# drive_pcb.net
KiCad netlist of a schematic drawn in EAGLE
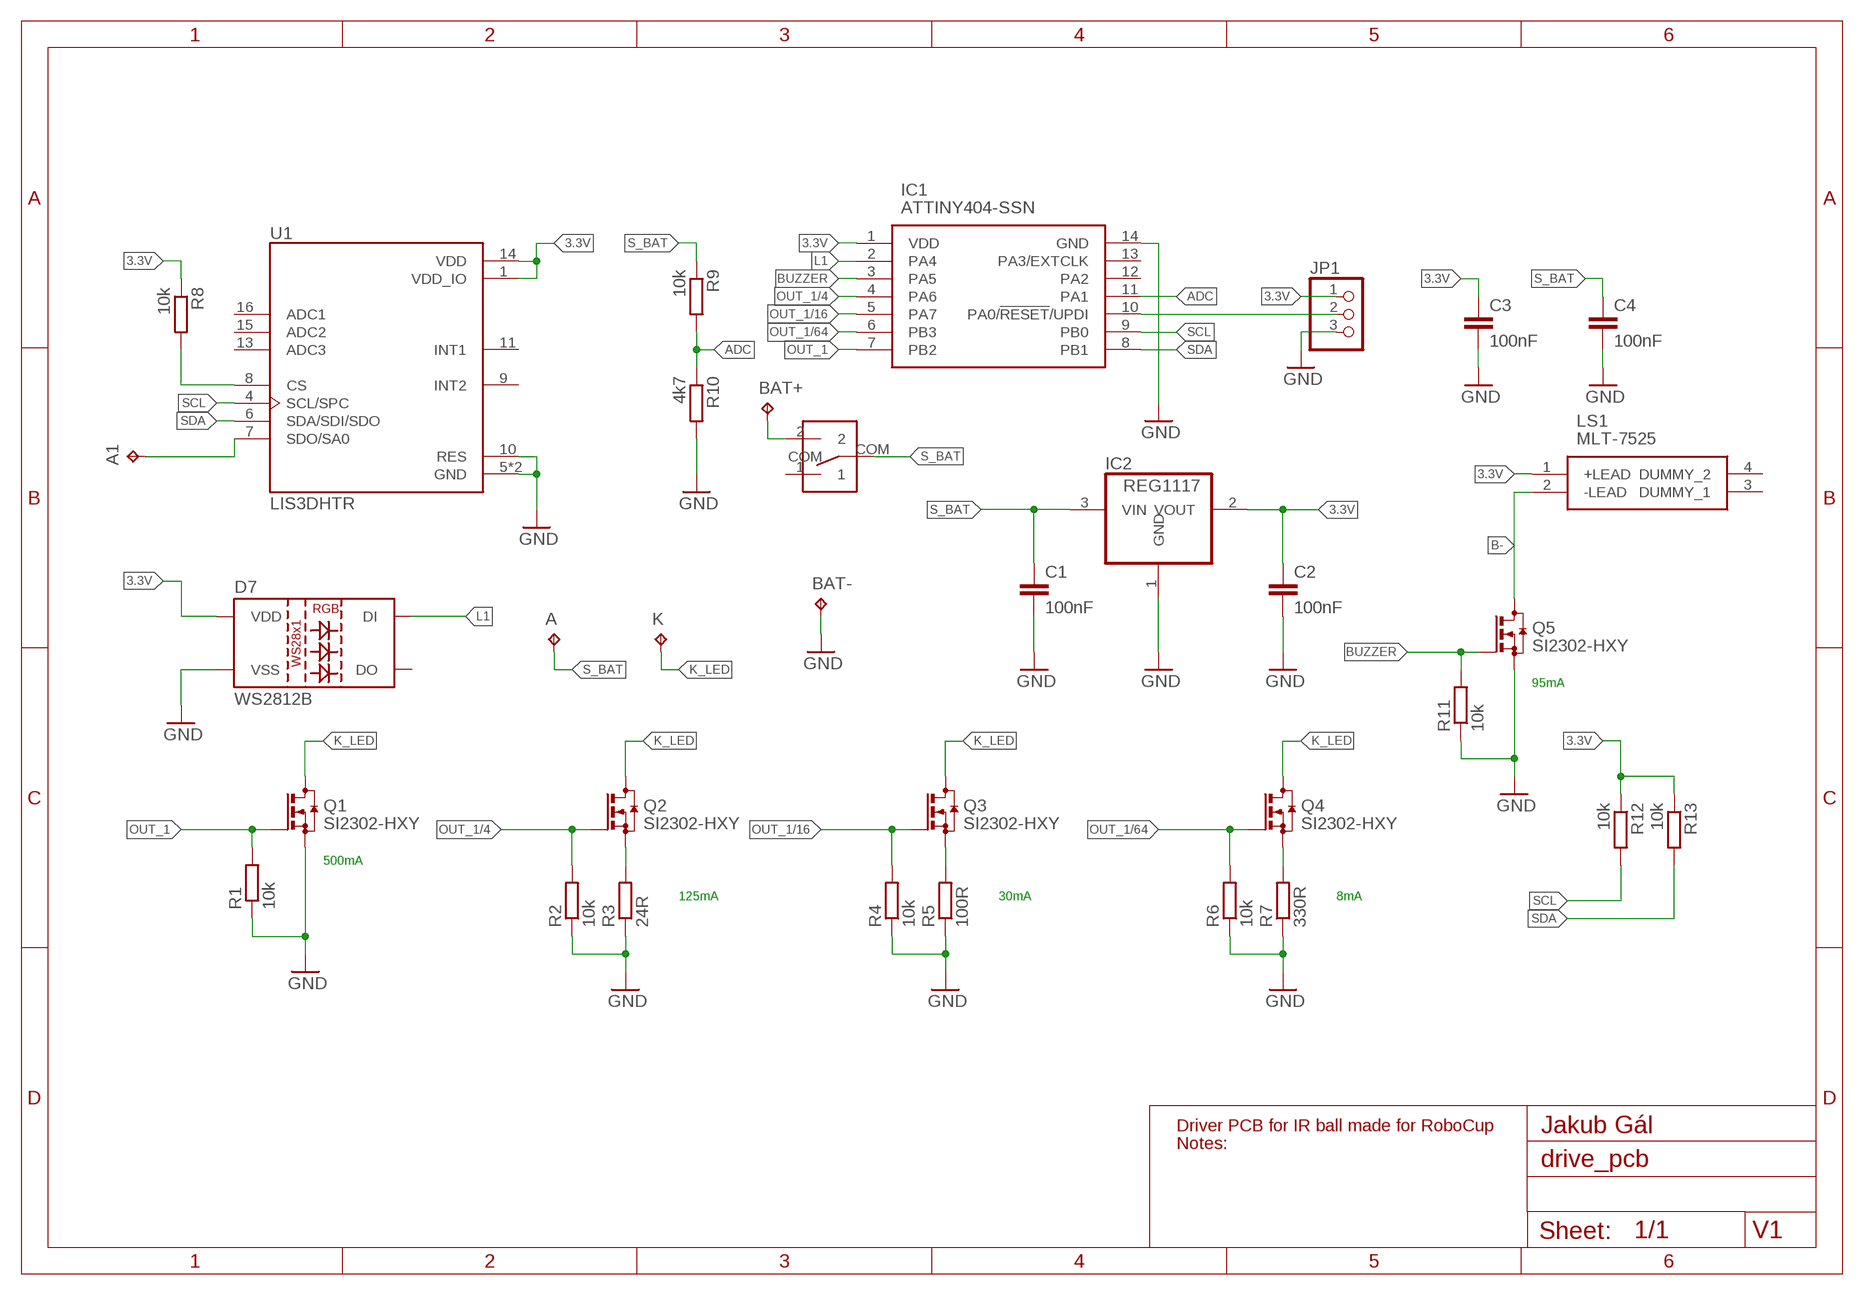
[diagram p0: schematic, sheet 1]

(export (version "E")
  (design (tool "Eeschema 10.0.6"))
  (components
    (comp (ref "A")
      (value "TPB1,27")
      (footprint "eagle-import:B1,27")
      (libsource (lib "eagle-import") (part "TPB1,27"))
    )
    (comp (ref "A1")
      (value "TPB1,27")
      (footprint "eagle-import:B1,27")
      (libsource (lib "eagle-import") (part "TPB1,27"))
    )
    (comp (ref "BAT+")
      (value "TPB1,27")
      (footprint "eagle-import:B1,27")
      (libsource (lib "eagle-import") (part "TPB1,27"))
    )
    (comp (ref "BAT-")
      (value "TPB1,27")
      (footprint "eagle-import:B1,27")
      (libsource (lib "eagle-import") (part "TPB1,27"))
    )
    (comp (ref "C1")
      (value "100nF")
      (footprint "eagle-import:C0603")
      (libsource (lib "eagle-import") (part "C-EUC0603"))
    )
    (comp (ref "C2")
      (value "100nF")
      (footprint "eagle-import:C0603")
      (libsource (lib "eagle-import") (part "C-EUC0603"))
    )
    (comp (ref "C3")
      (value "100nF")
      (footprint "eagle-import:C0603")
      (libsource (lib "eagle-import") (part "C-EUC0603"))
    )
    (comp (ref "C4")
      (value "100nF")
      (footprint "eagle-import:C0603")
      (libsource (lib "eagle-import") (part "C-EUC0603"))
    )
    (comp (ref "D7")
      (value "WS2812B")
      (footprint "eagle-import:WS2812B")
      (libsource (lib "eagle-import") (part "WS2812B"))
    )
    (comp (ref "IC1")
      (value "ATTINY404-SSN")
      (footprint "eagle-import:SOIC127P600X175-14N")
      (fields (field (name "MOUSER_PART_NUMBER") "579-ATTINY404-SSN"))
      (libsource (lib "eagle-import") (part "ATTINY404-SSN"))
    )
    (comp (ref "IC2")
      (value "REG1117")
      (footprint "eagle-import:SOT223")
      (libsource (lib "eagle-import") (part "REG1117"))
    )
    (comp (ref "JP1")
      (value "PINHD-1X3")
      (footprint "eagle-import:1X03")
      (libsource (lib "eagle-import") (part "PINHD-1X3"))
    )
    (comp (ref "K")
      (value "TPB1,27")
      (footprint "eagle-import:B1,27")
      (libsource (lib "eagle-import") (part "TPB1,27"))
    )
    (comp (ref "LS1")
      (value "MLT-7525")
      (footprint "eagle-import:MLT7525")
      (libsource (lib "eagle-import") (part "MLT-7525"))
    )
    (comp (ref "Q1")
      (value "SI2302-HXY")
      (footprint "eagle-import:SOT23")
      (libsource (lib "eagle-import") (part "BSS123"))
    )
    (comp (ref "Q2")
      (value "SI2302-HXY")
      (footprint "eagle-import:SOT23")
      (libsource (lib "eagle-import") (part "BSS123"))
    )
    (comp (ref "Q3")
      (value "SI2302-HXY")
      (footprint "eagle-import:SOT23")
      (libsource (lib "eagle-import") (part "BSS123"))
    )
    (comp (ref "Q4")
      (value "SI2302-HXY")
      (footprint "eagle-import:SOT23")
      (libsource (lib "eagle-import") (part "BSS123"))
    )
    (comp (ref "Q5")
      (value "SI2302-HXY")
      (footprint "eagle-import:SOT23")
      (libsource (lib "eagle-import") (part "BSS123"))
    )
    (comp (ref "R1")
      (value "10k")
      (footprint "eagle-import:R0603")
      (libsource (lib "eagle-import") (part "R-EU_R0603"))
    )
    (comp (ref "R2")
      (value "10k")
      (footprint "eagle-import:R0603")
      (libsource (lib "eagle-import") (part "R-EU_R0603"))
    )
    (comp (ref "R3")
      (value "24R")
      (footprint "eagle-import:R0603")
      (libsource (lib "eagle-import") (part "R-EU_R0603"))
    )
    (comp (ref "R4")
      (value "10k")
      (footprint "eagle-import:R0603")
      (libsource (lib "eagle-import") (part "R-EU_R0603"))
    )
    (comp (ref "R5")
      (value "100R")
      (footprint "eagle-import:R0603")
      (libsource (lib "eagle-import") (part "R-EU_R0603"))
    )
    (comp (ref "R6")
      (value "10k")
      (footprint "eagle-import:R0603")
      (libsource (lib "eagle-import") (part "R-EU_R0603"))
    )
    (comp (ref "R7")
      (value "330R")
      (footprint "eagle-import:R0603")
      (libsource (lib "eagle-import") (part "R-EU_R0603"))
    )
    (comp (ref "R8")
      (value "10k")
      (footprint "eagle-import:R0603")
      (libsource (lib "eagle-import") (part "R-EU_R0603"))
    )
    (comp (ref "R9")
      (value "10k")
      (footprint "eagle-import:R0603")
      (libsource (lib "eagle-import") (part "R-EU_R0603"))
    )
    (comp (ref "R10")
      (value "4k7")
      (footprint "eagle-import:R0603")
      (libsource (lib "eagle-import") (part "R-EU_R0603"))
    )
    (comp (ref "R11")
      (value "10k")
      (footprint "eagle-import:R0603")
      (libsource (lib "eagle-import") (part "R-EU_R0603"))
    )
    (comp (ref "R12")
      (value "10k")
      (footprint "eagle-import:R0603")
      (libsource (lib "eagle-import") (part "R-EU_R0603"))
    )
    (comp (ref "R13")
      (value "10k")
      (footprint "eagle-import:R0603")
      (libsource (lib "eagle-import") (part "R-EU_R0603"))
    )
    (comp (ref "U$1")
      (value "SK12D07VG4")
      (footprint "eagle-import:SK12D07VG4")
      (fields (field (name "MF") "C&K"))
      (libsource (lib "eagle-import") (part "SK12D07VG4"))
    )
    (comp (ref "U1")
      (value "LIS3DHTR")
      (footprint "eagle-import:XDCR_LIS3DHTR")
      (fields (field (name "MF") "STMicroelectronics"))
      (libsource (lib "eagle-import") (part "LIS3DHTR"))
    )
  )
  (nets
    (net (code "1") (name "3.3V") (class "Default")
      (node (ref "C2") (pin "1") (pinfunction "1_1") (pintype "passive"))
      (node (ref "C3") (pin "1") (pinfunction "1_1") (pintype "passive"))
      (node (ref "D7") (pin "1") (pinfunction "VDD_1") (pintype "bidirectional"))
      (node (ref "IC1") (pin "1") (pinfunction "VDD_1") (pintype "bidirectional"))
      (node (ref "IC2") (pin "2") (pinfunction "VOUT_2") (pintype "output"))
      (node (ref "JP1") (pin "1") (pinfunction "1_1") (pintype "passive"))
      (node (ref "LS1") (pin "1") (pinfunction "+LEAD_1") (pintype "bidirectional"))
      (node (ref "R12") (pin "1") (pinfunction "1_1") (pintype "passive"))
      (node (ref "R13") (pin "1") (pinfunction "1_1") (pintype "passive"))
      (node (ref "R8") (pin "1") (pinfunction "1_1") (pintype "passive"))
      (node (ref "U1") (pin "1") (pinfunction "VDD_IO_1") (pintype "power_in"))
      (node (ref "U1") (pin "14") (pinfunction "VDD_14") (pintype "power_in"))
    )
    (net (code "2") (name "ADC") (class "Default")
      (node (ref "IC1") (pin "11") (pinfunction "PA1_11") (pintype "bidirectional"))
      (node (ref "R10") (pin "1") (pinfunction "1_1") (pintype "passive"))
      (node (ref "R9") (pin "2") (pinfunction "2_2") (pintype "passive"))
    )
    (net (code "3") (name "B-") (class "Default")
      (node (ref "LS1") (pin "2") (pinfunction "-LEAD_2") (pintype "bidirectional"))
      (node (ref "Q5") (pin "3") (pinfunction "D_3") (pintype "passive"))
    )
    (net (code "4") (name "BUZZER") (class "Default")
      (node (ref "IC1") (pin "3") (pinfunction "PA5_3") (pintype "bidirectional"))
      (node (ref "Q5") (pin "1") (pinfunction "G_1") (pintype "passive"))
      (node (ref "R11") (pin "2") (pinfunction "2_2") (pintype "passive"))
    )
    (net (code "5") (name "GND") (class "Default")
      (node (ref "BAT-") (pin "TP") (pinfunction "TP_TP") (pintype "input"))
      (node (ref "C1") (pin "2") (pinfunction "2_2") (pintype "passive"))
      (node (ref "C2") (pin "2") (pinfunction "2_2") (pintype "passive"))
      (node (ref "C3") (pin "2") (pinfunction "2_2") (pintype "passive"))
      (node (ref "C4") (pin "2") (pinfunction "2_2") (pintype "passive"))
      (node (ref "D7") (pin "3") (pinfunction "VSS_3") (pintype "bidirectional"))
      (node (ref "IC1") (pin "14") (pinfunction "GND_14") (pintype "bidirectional"))
      (node (ref "IC2") (pin "1") (pinfunction "GND_1") (pintype "power_in"))
      (node (ref "JP1") (pin "3") (pinfunction "3_3") (pintype "passive"))
      (node (ref "Q1") (pin "2") (pinfunction "S_2") (pintype "passive"))
      (node (ref "Q5") (pin "2") (pinfunction "S_2") (pintype "passive"))
      (node (ref "R1") (pin "1") (pinfunction "1_1") (pintype "passive"))
      (node (ref "R10") (pin "2") (pinfunction "2_2") (pintype "passive"))
      (node (ref "R11") (pin "1") (pinfunction "1_1") (pintype "passive"))
      (node (ref "R2") (pin "1") (pinfunction "1_1") (pintype "passive"))
      (node (ref "R3") (pin "1") (pinfunction "1_1") (pintype "passive"))
      (node (ref "R4") (pin "1") (pinfunction "1_1") (pintype "passive"))
      (node (ref "R5") (pin "1") (pinfunction "1_1") (pintype "passive"))
      (node (ref "R6") (pin "1") (pinfunction "1_1") (pintype "passive"))
      (node (ref "R7") (pin "1") (pinfunction "1_1") (pintype "passive"))
      (node (ref "U1") (pin "10") (pinfunction "RES_10") (pintype "passive"))
      (node (ref "U1") (pin "12") (pinfunction "GND_12") (pintype "power_in"))
      (node (ref "U1") (pin "5") (pinfunction "GND_5") (pintype "power_in"))
    )
    (net (code "6") (name "K_LED") (class "Default")
      (node (ref "K") (pin "TP") (pinfunction "TP_TP") (pintype "input"))
      (node (ref "Q1") (pin "3") (pinfunction "D_3") (pintype "passive"))
      (node (ref "Q2") (pin "3") (pinfunction "D_3") (pintype "passive"))
      (node (ref "Q3") (pin "3") (pinfunction "D_3") (pintype "passive"))
      (node (ref "Q4") (pin "3") (pinfunction "D_3") (pintype "passive"))
    )
    (net (code "7") (name "L1") (class "Default")
      (node (ref "D7") (pin "4") (pinfunction "DI_4") (pintype "bidirectional"))
      (node (ref "IC1") (pin "2") (pinfunction "PA4_2") (pintype "bidirectional"))
    )
    (net (code "8") (name "Net-(BAT+-PadTP)") (class "Default")
      (node (ref "BAT+") (pin "TP") (pinfunction "TP_TP") (pintype "input"))
      (node (ref "U$1") (pin "2") (pinfunction "2_2") (pintype "bidirectional"))
    )
    (net (code "9") (name "Net-(IC1-PA0{slash}~{RESET}{slash}UPDI)") (class "Default")
      (node (ref "IC1") (pin "10") (pinfunction "PA0/~{RESET}/UPDI_10") (pintype "bidirectional"))
      (node (ref "JP1") (pin "2") (pinfunction "2_2") (pintype "passive"))
    )
    (net (code "10") (name "Net-(Q2-S)") (class "Default")
      (node (ref "Q2") (pin "2") (pinfunction "S_2") (pintype "passive"))
      (node (ref "R3") (pin "2") (pinfunction "2_2") (pintype "passive"))
    )
    (net (code "11") (name "Net-(Q3-S)") (class "Default")
      (node (ref "Q3") (pin "2") (pinfunction "S_2") (pintype "passive"))
      (node (ref "R5") (pin "2") (pinfunction "2_2") (pintype "passive"))
    )
    (net (code "12") (name "Net-(Q4-S)") (class "Default")
      (node (ref "Q4") (pin "2") (pinfunction "S_2") (pintype "passive"))
      (node (ref "R7") (pin "2") (pinfunction "2_2") (pintype "passive"))
    )
    (net (code "13") (name "Net-(U1-CS)") (class "Default")
      (node (ref "R8") (pin "2") (pinfunction "2_2") (pintype "passive"))
      (node (ref "U1") (pin "8") (pinfunction "CS_8") (pintype "input"))
    )
    (net (code "14") (name "Net-(U1-SDO{slash}SA0)") (class "Default")
      (node (ref "A1") (pin "TP") (pinfunction "TP_TP") (pintype "input"))
      (node (ref "U1") (pin "7") (pinfunction "SDO/SA0_7") (pintype "bidirectional"))
    )
    (net (code "15") (name "OUT_1") (class "Default")
      (node (ref "IC1") (pin "7") (pinfunction "PB2_7") (pintype "bidirectional"))
      (node (ref "Q1") (pin "1") (pinfunction "G_1") (pintype "passive"))
      (node (ref "R1") (pin "2") (pinfunction "2_2") (pintype "passive"))
    )
    (net (code "16") (name "OUT_1{slash}4") (class "Default")
      (node (ref "IC1") (pin "4") (pinfunction "PA6_4") (pintype "bidirectional"))
      (node (ref "Q2") (pin "1") (pinfunction "G_1") (pintype "passive"))
      (node (ref "R2") (pin "2") (pinfunction "2_2") (pintype "passive"))
    )
    (net (code "17") (name "OUT_1{slash}16") (class "Default")
      (node (ref "IC1") (pin "5") (pinfunction "PA7_5") (pintype "bidirectional"))
      (node (ref "Q3") (pin "1") (pinfunction "G_1") (pintype "passive"))
      (node (ref "R4") (pin "2") (pinfunction "2_2") (pintype "passive"))
    )
    (net (code "18") (name "OUT_1{slash}64") (class "Default")
      (node (ref "IC1") (pin "6") (pinfunction "PB3_6") (pintype "bidirectional"))
      (node (ref "Q4") (pin "1") (pinfunction "G_1") (pintype "passive"))
      (node (ref "R6") (pin "2") (pinfunction "2_2") (pintype "passive"))
    )
    (net (code "19") (name "SCL") (class "Default")
      (node (ref "IC1") (pin "9") (pinfunction "PB0_9") (pintype "bidirectional"))
      (node (ref "R12") (pin "2") (pinfunction "2_2") (pintype "passive"))
      (node (ref "U1") (pin "4") (pinfunction "SCL/SPC_4") (pintype "input"))
    )
    (net (code "20") (name "SDA") (class "Default")
      (node (ref "IC1") (pin "8") (pinfunction "PB1_8") (pintype "bidirectional"))
      (node (ref "R13") (pin "2") (pinfunction "2_2") (pintype "passive"))
      (node (ref "U1") (pin "6") (pinfunction "SDA/SDI/SDO_6") (pintype "bidirectional"))
    )
    (net (code "21") (name "S_BAT") (class "Default")
      (node (ref "A") (pin "TP") (pinfunction "TP_TP") (pintype "input"))
      (node (ref "C1") (pin "1") (pinfunction "1_1") (pintype "passive"))
      (node (ref "C4") (pin "1") (pinfunction "1_1") (pintype "passive"))
      (node (ref "IC2") (pin "3") (pinfunction "VIN_3") (pintype "input"))
      (node (ref "R9") (pin "1") (pinfunction "1_1") (pintype "passive"))
      (node (ref "U$1") (pin "COM") (pinfunction "COM_COM") (pintype "bidirectional"))
    )
    (net (code "22") (name "unconnected-(D7-DO-Pad2)") (class "Default")
      (node (ref "D7") (pin "2") (pinfunction "DO_2") (pintype "bidirectional"))
    )
    (net (code "23") (name "unconnected-(IC1-PA2-Pad12)") (class "Default")
      (node (ref "IC1") (pin "12") (pinfunction "PA2_12") (pintype "bidirectional"))
    )
    (net (code "24") (name "unconnected-(IC1-PA3{slash}EXTCLK-Pad13)") (class "Default")
      (node (ref "IC1") (pin "13") (pinfunction "PA3/EXTCLK_13") (pintype "bidirectional"))
    )
    (net (code "25") (name "unconnected-(LS1-DUMMY_1-Pad3)") (class "Default")
      (node (ref "LS1") (pin "3") (pinfunction "DUMMY_1_3") (pintype "bidirectional"))
    )
    (net (code "26") (name "unconnected-(LS1-DUMMY_2-Pad4)") (class "Default")
      (node (ref "LS1") (pin "4") (pinfunction "DUMMY_2_4") (pintype "bidirectional"))
    )
    (net (code "27") (name "unconnected-(U$1-Pad1)") (class "Default")
      (node (ref "U$1") (pin "1") (pinfunction "1_1") (pintype "bidirectional"))
    )
    (net (code "28") (name "unconnected-(U1-ADC1-Pad16)") (class "Default")
      (node (ref "U1") (pin "16") (pinfunction "ADC1_16") (pintype "input"))
    )
    (net (code "29") (name "unconnected-(U1-ADC2-Pad15)") (class "Default")
      (node (ref "U1") (pin "15") (pinfunction "ADC2_15") (pintype "input"))
    )
    (net (code "30") (name "unconnected-(U1-ADC3-Pad13)") (class "Default")
      (node (ref "U1") (pin "13") (pinfunction "ADC3_13") (pintype "input"))
    )
    (net (code "31") (name "unconnected-(U1-INT1-Pad11)") (class "Default")
      (node (ref "U1") (pin "11") (pinfunction "INT1_11") (pintype "output"))
    )
    (net (code "32") (name "unconnected-(U1-INT2-Pad9)") (class "Default")
      (node (ref "U1") (pin "9") (pinfunction "INT2_9") (pintype "output"))
    )
  )
)
